# FinalAQsensors.net
KiCad netlist of a schematic drawn in EAGLE
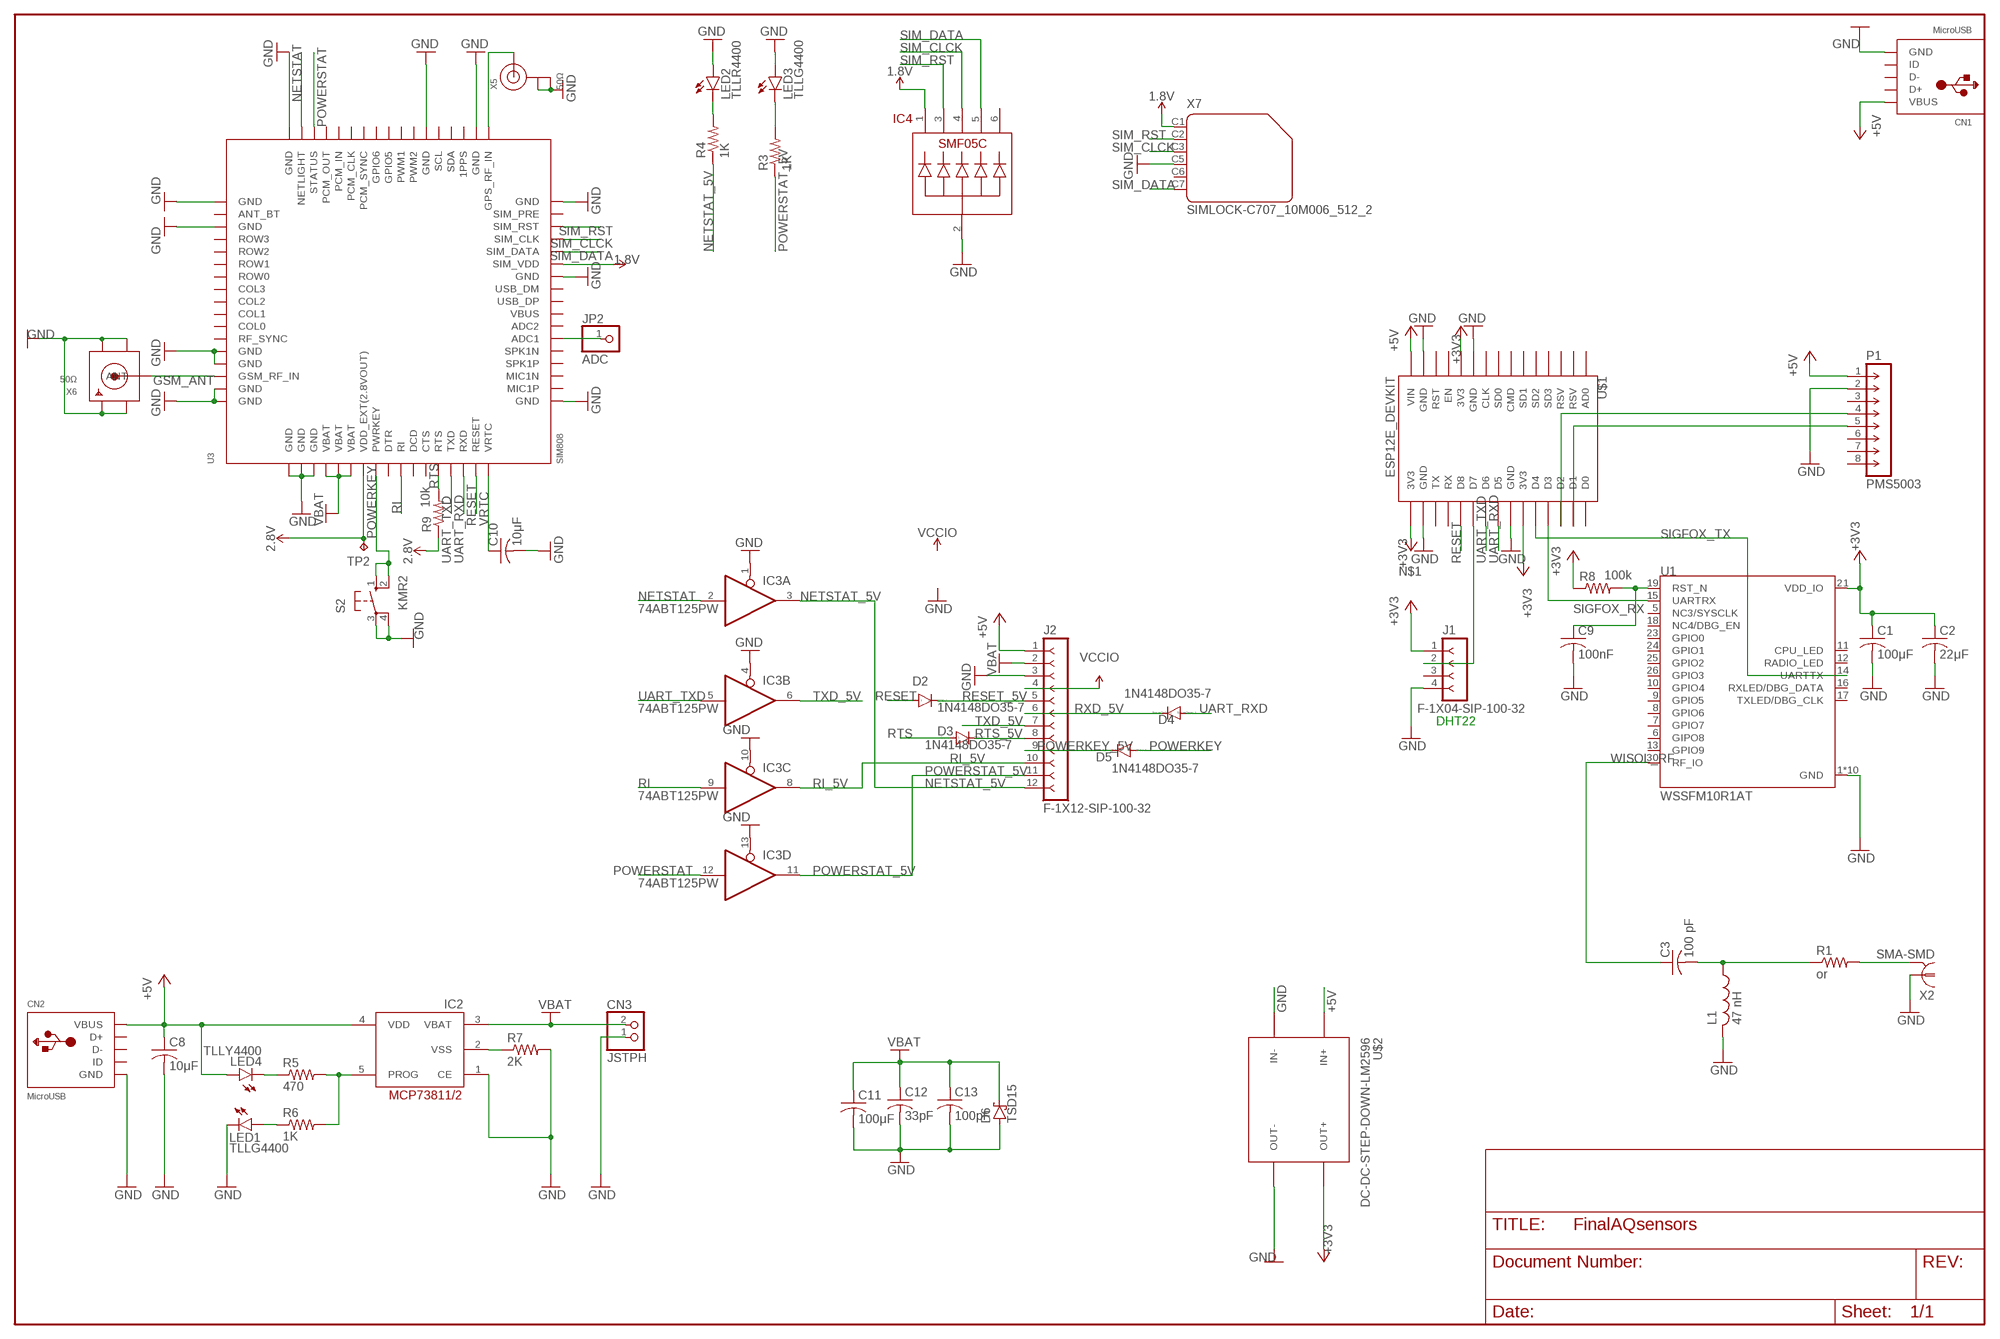
[diagram p0: schematic, sheet 1]

(export (version "E")
  (design (tool "Eeschema 10.0.6"))
  (components
    (comp (ref "C1")
      (value "100μF")
      (footprint "eagle-import:C0201")
      (libsource (lib "eagle-import") (part "C-USC0201"))
    )
    (comp (ref "C2")
      (value "22μF")
      (footprint "eagle-import:C0201")
      (libsource (lib "eagle-import") (part "C-USC0201"))
    )
    (comp (ref "C3")
      (value "100 pF")
      (footprint "eagle-import:C0201")
      (libsource (lib "eagle-import") (part "C-USC0201"))
    )
    (comp (ref "C8")
      (value "10μF")
      (footprint "eagle-import:C025-025X050")
      (libsource (lib "eagle-import") (part "C-US025-025X050"))
    )
    (comp (ref "C9")
      (value "100nF")
      (footprint "eagle-import:C025-025X050")
      (libsource (lib "eagle-import") (part "rcl_334_C-US025-025X050"))
    )
    (comp (ref "C10")
      (value "10μF")
      (footprint "eagle-import:C0402")
      (libsource (lib "eagle-import") (part "rcl_334_C-USC0402"))
    )
    (comp (ref "C11")
      (value "100μF")
      (footprint "eagle-import:C0402")
      (libsource (lib "eagle-import") (part "rcl_334_C-USC0402"))
    )
    (comp (ref "C12")
      (value "33pF")
      (footprint "eagle-import:C0402")
      (libsource (lib "eagle-import") (part "rcl_334_C-USC0402"))
    )
    (comp (ref "C13")
      (value "100pF")
      (footprint "eagle-import:C0402")
      (libsource (lib "eagle-import") (part "rcl_334_C-USC0402"))
    )
    (comp (ref "CN1")
      (value "MicroUSB")
      (footprint "eagle-import:USB-MINIB")
      (libsource (lib "eagle-import") (part "adafruit_420_USBMINIB"))
    )
    (comp (ref "CN2")
      (value "MicroUSB")
      (footprint "eagle-import:USB-MINIB")
      (libsource (lib "eagle-import") (part "USBMINIB"))
    )
    (comp (ref "CN3")
      (value "JSTPH")
      (footprint "eagle-import:JST-PH-2-SMT")
      (libsource (lib "eagle-import") (part "JST_2PIN-SMT"))
    )
    (comp (ref "D2")
      (value "1N4148DO35-7")
      (footprint "eagle-import:DO35-7")
      (libsource (lib "eagle-import") (part "1N4148DO35-7"))
    )
    (comp (ref "D3")
      (value "1N4148DO35-7")
      (footprint "eagle-import:DO35-7")
      (libsource (lib "eagle-import") (part "1N4148DO35-7"))
    )
    (comp (ref "D4")
      (value "1N4148DO35-7")
      (footprint "eagle-import:DO35-7")
      (libsource (lib "eagle-import") (part "1N4148DO35-7"))
    )
    (comp (ref "D5")
      (value "1N4148DO35-7")
      (footprint "eagle-import:DO35-7")
      (libsource (lib "eagle-import") (part "1N4148DO35-7"))
    )
    (comp (ref "D6")
      (value "TSD15")
      (footprint "eagle-import:CB429-15")
      (libsource (lib "eagle-import") (part "TSD15"))
    )
    (comp (ref "IC2")
      (value "MCP73811/2")
      (footprint "eagle-import:SOT23-5L")
      (libsource (lib "eagle-import") (part "MCP73811/2"))
    )
    (comp (ref "IC3")
      (value "74ABT125PW")
      (footprint "eagle-import:TSSOP14")
      (libsource (lib "eagle-import") (part "74125PWABT"))
    )
    (comp (ref "IC4")
      (value "SMF05C")
      (footprint "eagle-import:SC-70-6")
      (libsource (lib "eagle-import") (part "SMF05C"))
    )
    (comp (ref "J1")
      (value "F-1X04-SIP-100-32")
      (footprint "eagle-import:SIP-100-04-32")
      (libsource (lib "eagle-import") (part "F-1X04-SIP-100-32"))
    )
    (comp (ref "J2")
      (value "F-1X12-SIP-100-32")
      (footprint "eagle-import:SIP-100-12-32")
      (libsource (lib "eagle-import") (part "F-1X12-SIP-100-32"))
    )
    (comp (ref "JP2")
      (value "ADC")
      (footprint "eagle-import:1X01M")
      (libsource (lib "eagle-import") (part "PINHD-1X01_2.00"))
    )
    (comp (ref "L1")
      (value "47 nH")
      (footprint "eagle-import:0204_7")
      (libsource (lib "eagle-import") (part "L-US0204/7"))
    )
    (comp (ref "LED1")
      (value "TLLG4400")
      (footprint "eagle-import:LED3MM")
      (fields (field (name "MF") "VISHAY SEMICONDUCTOR"))
      (libsource (lib "eagle-import") (part "TLLG4400"))
    )
    (comp (ref "LED2")
      (value "TLLR4400")
      (footprint "eagle-import:LED3MM")
      (fields (field (name "MF") "VISHAY SEMICONDUCTOR"))
      (libsource (lib "eagle-import") (part "TLLR4400"))
    )
    (comp (ref "LED3")
      (value "TLLG4400")
      (footprint "eagle-import:LED3MM")
      (fields (field (name "MF") "VISHAY SEMICONDUCTOR"))
      (libsource (lib "eagle-import") (part "TLLG4400"))
    )
    (comp (ref "LED4")
      (value "TLLY4400")
      (footprint "eagle-import:LED3MM")
      (fields (field (name "MF") "VISHAY SEMICONDUCTOR"))
      (libsource (lib "eagle-import") (part "TLLY4400"))
    )
    (comp (ref "P1")
      (value "PMS5003")
      (footprint "eagle-import:SIP-100-08-40")
      (libsource (lib "eagle-import") (part "M-1X08-SIP-100-40"))
    )
    (comp (ref "R1")
      (value "or")
      (footprint "eagle-import:0204_5")
      (libsource (lib "eagle-import") (part "R-US_0204/5"))
    )
    (comp (ref "R3")
      (value "1K")
      (footprint "eagle-import:0204_5")
      (libsource (lib "eagle-import") (part "R-US_0204/5"))
    )
    (comp (ref "R4")
      (value "1K")
      (footprint "eagle-import:0204_5")
      (libsource (lib "eagle-import") (part "R-US_0204/5"))
    )
    (comp (ref "R5")
      (value "470")
      (footprint "eagle-import:0204_5")
      (libsource (lib "eagle-import") (part "R-US_0204/5"))
    )
    (comp (ref "R6")
      (value "1K")
      (footprint "eagle-import:0204_5")
      (libsource (lib "eagle-import") (part "R-US_0204/5"))
    )
    (comp (ref "R7")
      (value "2K")
      (footprint "eagle-import:0204_5")
      (libsource (lib "eagle-import") (part "R-US_0204/5"))
    )
    (comp (ref "R8")
      (value "100k")
      (footprint "eagle-import:0204_7")
      (libsource (lib "eagle-import") (part "R-US_0204/7"))
    )
    (comp (ref "R9")
      (value "10k")
      (footprint "eagle-import:0204_5")
      (libsource (lib "eagle-import") (part "R-US_0204/5"))
    )
    (comp (ref "S2")
      (value "KMR2")
      (footprint "eagle-import:B3F_40XX")
      (libsource (lib "eagle-import") (part "40/XX"))
    )
    (comp (ref "TP2")
      (value "TPTP10R")
      (footprint "eagle-import:TP10R")
      (libsource (lib "eagle-import") (part "TPTP10R"))
    )
    (comp (ref "U$1")
      (value "ESP12E_DEVKIT")
      (footprint "eagle-import:ESP12E_DEVKIT")
      (libsource (lib "eagle-import") (part "ESP12E_DEVKIT"))
    )
    (comp (ref "U$2")
      (value "DC-DC-STEP-DOWN-LM2596")
      (footprint "eagle-import:DC-DC-STEP-DOWN-LM2596")
      (libsource (lib "eagle-import") (part "DC-DC-STEP-DOWN-LM2596"))
    )
    (comp (ref "U1")
      (value "WSSFM10R1AT")
      (footprint "eagle-import:XCVR_WSSFM10R1AT")
      (fields (field (name "MF") "Avnet Design Services"))
      (libsource (lib "eagle-import") (part "WSSFM10R1AT"))
    )
    (comp (ref "U3")
      (value "SIM808")
      (footprint "eagle-import:SIM900_SMT")
      (libsource (lib "eagle-import") (part "GSM_SIM808_LITERAL"))
    )
    (comp (ref "X2")
      (value "SMA-SMD")
      (footprint "eagle-import:SMA-SMD")
      (libsource (lib "eagle-import") (part "SMA-SMD"))
    )
    (comp (ref "X5")
      (value "50Ω")
      (footprint "eagle-import:U.FL")
      (libsource (lib "eagle-import") (part "ANTENNA_U.FL"))
    )
    (comp (ref "X6")
      (value "50Ω")
      (footprint "eagle-import:SMA_EDGELAUNCH_UFL")
      (libsource (lib "eagle-import") (part "SMACONNECTOR_EDGE_UFL"))
    )
    (comp (ref "X7")
      (value "SIMLOCK-C707_10M006_512_2")
      (footprint "eagle-import:C707_10M006_512_2")
      (libsource (lib "eagle-import") (part "SIMLOCK-C707_10M006_512_2"))
    )
  )
  (nets
    (net (code "1") (name "+3V3") (class "Default")
      (node (ref "C1") (pin "1") (pinfunction "1_1") (pintype "passive"))
      (node (ref "C2") (pin "1") (pinfunction "1_1") (pintype "passive"))
      (node (ref "J1") (pin "1") (pinfunction "1_1") (pintype "passive"))
      (node (ref "R8") (pin "1") (pinfunction "1_1") (pintype "passive"))
      (node (ref "U$1") (pin "3V3@0") (pinfunction "3V3_3V3@0") (pintype "bidirectional"))
      (node (ref "U$1") (pin "3V3@1") (pinfunction "3V3_3V3@1") (pintype "bidirectional"))
      (node (ref "U$1") (pin "3V3@2") (pinfunction "3V3_3V3@2") (pintype "bidirectional"))
      (node (ref "U$2") (pin "OUT+") (pinfunction "OUT+_OUT+") (pintype "bidirectional"))
      (node (ref "U1") (pin "21") (pinfunction "VDD_IO_21") (pintype "power_in"))
    )
    (net (code "2") (name "+5V") (class "Default")
      (node (ref "C8") (pin "1") (pinfunction "1_1") (pintype "passive"))
      (node (ref "CN1") (pin "VBUS") (pinfunction "VBUS_VBUS") (pintype "power_in"))
      (node (ref "CN2") (pin "VBUS") (pinfunction "VBUS_VBUS") (pintype "power_in"))
      (node (ref "IC2") (pin "4") (pinfunction "VDD_4") (pintype "power_in"))
      (node (ref "J2") (pin "1") (pinfunction "1_1") (pintype "passive"))
      (node (ref "LED4") (pin "A") (pinfunction "A_A") (pintype "passive"))
      (node (ref "P1") (pin "1") (pinfunction "1_1") (pintype "passive"))
      (node (ref "U$1") (pin "VIN") (pinfunction "VIN_VIN") (pintype "bidirectional"))
      (node (ref "U$2") (pin "IN+") (pinfunction "IN+_IN+") (pintype "bidirectional"))
    )
    (net (code "3") (name "/GSM_ANT") (class "Default")
      (node (ref "U3") (pin "P$66") (pinfunction "GSM_RF_IN_P$66") (pintype "input"))
      (node (ref "X6") (pin "P") (pinfunction "ANT_P") (pintype "bidirectional"))
    )
    (net (code "4") (name "/N$1") (class "Default")
      (node (ref "J1") (pin "2") (pinfunction "2_2") (pintype "passive"))
      (node (ref "U$1") (pin "D7") (pinfunction "D7_D7") (pintype "bidirectional"))
    )
    (net (code "5") (name "/NETSTAT") (class "Default")
      (node (ref "IC3") (pin "2") (pinfunction "I_2") (pintype "input"))
      (node (ref "U3") (pin "P$50") (pinfunction "NETLIGHT_P$50") (pintype "output"))
    )
    (net (code "6") (name "/NETSTAT_5V") (class "Default")
      (node (ref "IC3") (pin "3") (pinfunction "O_3") (pintype "tri_state"))
      (node (ref "J2") (pin "12") (pinfunction "12_12") (pintype "passive"))
      (node (ref "R4") (pin "1") (pinfunction "1_1") (pintype "passive"))
    )
    (net (code "7") (name "/POWERKEY") (class "Default")
      (node (ref "D5") (pin "A") (pinfunction "A_A") (pintype "passive"))
      (node (ref "S2") (pin "1") (pinfunction "S_1") (pintype "passive"))
      (node (ref "S2") (pin "2") (pinfunction "S1_2") (pintype "passive"))
      (node (ref "U3") (pin "P$8") (pinfunction "PWRKEY_P$8") (pintype "input"))
    )
    (net (code "8") (name "/POWERKEY_5V") (class "Default")
      (node (ref "D5") (pin "C") (pinfunction "C_C") (pintype "passive"))
      (node (ref "J2") (pin "9") (pinfunction "9_9") (pintype "passive"))
    )
    (net (code "9") (name "/POWERSTAT") (class "Default")
      (node (ref "IC3") (pin "12") (pinfunction "I_12") (pintype "input"))
      (node (ref "U3") (pin "P$49") (pinfunction "STATUS_P$49") (pintype "output"))
    )
    (net (code "10") (name "/POWERSTAT_5V") (class "Default")
      (node (ref "IC3") (pin "11") (pinfunction "O_11") (pintype "tri_state"))
      (node (ref "J2") (pin "11") (pinfunction "11_11") (pintype "passive"))
      (node (ref "R3") (pin "1") (pinfunction "1_1") (pintype "passive"))
    )
    (net (code "11") (name "/RESET") (class "Default")
      (node (ref "D2") (pin "A") (pinfunction "A_A") (pintype "passive"))
      (node (ref "U$1") (pin "D8") (pinfunction "D8_D8") (pintype "bidirectional"))
      (node (ref "U3") (pin "P$16") (pinfunction "RESET_P$16") (pintype "input"))
    )
    (net (code "12") (name "/RESET_5V") (class "Default")
      (node (ref "D2") (pin "C") (pinfunction "C_C") (pintype "passive"))
      (node (ref "J2") (pin "5") (pinfunction "5_5") (pintype "passive"))
    )
    (net (code "13") (name "/RI") (class "Default")
      (node (ref "IC3") (pin "9") (pinfunction "I_9") (pintype "input"))
      (node (ref "U3") (pin "P$10") (pinfunction "RI_P$10") (pintype "output"))
    )
    (net (code "14") (name "/RI_5V") (class "Default")
      (node (ref "IC3") (pin "8") (pinfunction "O_8") (pintype "tri_state"))
      (node (ref "J2") (pin "10") (pinfunction "10_10") (pintype "passive"))
    )
    (net (code "15") (name "/RTS") (class "Default")
      (node (ref "D3") (pin "A") (pinfunction "A_A") (pintype "passive"))
      (node (ref "R9") (pin "2") (pinfunction "2_2") (pintype "passive"))
      (node (ref "U3") (pin "P$13") (pinfunction "RTS_P$13") (pintype "input"))
    )
    (net (code "16") (name "/RTS_5V") (class "Default")
      (node (ref "D3") (pin "C") (pinfunction "C_C") (pintype "passive"))
      (node (ref "J2") (pin "8") (pinfunction "8_8") (pintype "passive"))
    )
    (net (code "17") (name "/RXD_5V") (class "Default")
      (node (ref "D4") (pin "C") (pinfunction "C_C") (pintype "passive"))
      (node (ref "J2") (pin "6") (pinfunction "6_6") (pintype "passive"))
    )
    (net (code "18") (name "/SIGFOX_RX") (class "Default")
      (node (ref "U$1") (pin "D3") (pinfunction "D3_D3") (pintype "bidirectional"))
      (node (ref "U1") (pin "15") (pinfunction "UARTRX_15") (pintype "input"))
    )
    (net (code "19") (name "/SIGFOX_TX") (class "Default")
      (node (ref "U$1") (pin "D4") (pinfunction "D4_D4") (pintype "bidirectional"))
      (node (ref "U1") (pin "14") (pinfunction "UARTTX_14") (pintype "output"))
    )
    (net (code "20") (name "/SIM_CLCK") (class "Default")
      (node (ref "IC4") (pin "4") (pinfunction "4_4") (pintype "bidirectional"))
      (node (ref "U3") (pin "P$31") (pinfunction "SIM_CLK_P$31") (pintype "output"))
      (node (ref "X7") (pin "C3") (pinfunction "3_C3") (pintype "passive"))
    )
    (net (code "21") (name "/SIM_DATA") (class "Default")
      (node (ref "IC4") (pin "5") (pinfunction "5_5") (pintype "bidirectional"))
      (node (ref "U3") (pin "P$30") (pinfunction "SIM_DATA_P$30") (pintype "bidirectional"))
      (node (ref "X7") (pin "C7") (pinfunction "6_C7") (pintype "passive"))
    )
    (net (code "22") (name "/SIM_RST") (class "Default")
      (node (ref "IC4") (pin "3") (pinfunction "3_3") (pintype "bidirectional"))
      (node (ref "U3") (pin "P$32") (pinfunction "SIM_RST_P$32") (pintype "output"))
      (node (ref "X7") (pin "C2") (pinfunction "2_C2") (pintype "passive"))
    )
    (net (code "23") (name "/TXD_5V") (class "Default")
      (node (ref "IC3") (pin "6") (pinfunction "O_6") (pintype "tri_state"))
      (node (ref "J2") (pin "7") (pinfunction "7_7") (pintype "passive"))
    )
    (net (code "24") (name "/UART_RXD") (class "Default")
      (node (ref "D4") (pin "A") (pinfunction "A_A") (pintype "passive"))
      (node (ref "U$1") (pin "D5") (pinfunction "D5_D5") (pintype "bidirectional"))
      (node (ref "U3") (pin "P$15") (pinfunction "RXD_P$15") (pintype "input"))
    )
    (net (code "25") (name "/UART_TXD") (class "Default")
      (node (ref "IC3") (pin "5") (pinfunction "I_5") (pintype "input"))
      (node (ref "U$1") (pin "D6") (pinfunction "D6_D6") (pintype "bidirectional"))
      (node (ref "U3") (pin "P$14") (pinfunction "TXD_P$14") (pintype "output"))
    )
    (net (code "26") (name "/VBUS") (class "Default")
      (node (ref "U3") (pin "P$25") (pinfunction "VBUS_P$25") (pintype "power_in"))
    )
    (net (code "27") (name "/VRTC") (class "Default")
      (node (ref "C10") (pin "1") (pinfunction "1_1") (pintype "passive"))
      (node (ref "U3") (pin "P$17") (pinfunction "VRTC_P$17") (pintype "power_in"))
    )
    (net (code "28") (name "/WISOL_RF") (class "Default")
      (node (ref "C3") (pin "1") (pinfunction "1_1") (pintype "passive"))
      (node (ref "U1") (pin "30") (pinfunction "RF_IO_30") (pintype "bidirectional"))
    )
    (net (code "29") (name "1.8V") (class "Default")
      (node (ref "IC4") (pin "1") (pinfunction "1_1") (pintype "bidirectional"))
      (node (ref "U3") (pin "P$29") (pinfunction "SIM_VDD_P$29") (pintype "power_in"))
      (node (ref "X7") (pin "C1") (pinfunction "1_C1") (pintype "passive"))
    )
    (net (code "30") (name "2.8V") (class "Default")
      (node (ref "R9") (pin "1") (pinfunction "1_1") (pintype "passive"))
      (node (ref "TP2") (pin "TP") (pinfunction "TP_TP") (pintype "input"))
      (node (ref "U3") (pin "P$7") (pinfunction "VDD_EXT(2.8VOUT)_P$7") (pintype "power_in"))
    )
    (net (code "31") (name "GND") (class "Default")
      (node (ref "C1") (pin "2") (pinfunction "2_2") (pintype "passive"))
      (node (ref "C10") (pin "2") (pinfunction "2_2") (pintype "passive"))
      (node (ref "C11") (pin "2") (pinfunction "2_2") (pintype "passive"))
      (node (ref "C12") (pin "2") (pinfunction "2_2") (pintype "passive"))
      (node (ref "C13") (pin "2") (pinfunction "2_2") (pintype "passive"))
      (node (ref "C2") (pin "2") (pinfunction "2_2") (pintype "passive"))
      (node (ref "C8") (pin "2") (pinfunction "2_2") (pintype "passive"))
      (node (ref "C9") (pin "2") (pinfunction "2_2") (pintype "passive"))
      (node (ref "CN1") (pin "GND") (pinfunction "GND_GND") (pintype "power_in"))
      (node (ref "CN2") (pin "GND") (pinfunction "GND_GND") (pintype "power_in"))
      (node (ref "CN3") (pin "1") (pinfunction "2_1") (pintype "passive"))
      (node (ref "D6") (pin "A") (pinfunction "A_A") (pintype "passive"))
      (node (ref "IC2") (pin "1") (pinfunction "CE_1") (pintype "input"))
      (node (ref "IC3") (pin "1") (pinfunction "OE_1") (pintype "input"))
      (node (ref "IC3") (pin "10") (pinfunction "OE_10") (pintype "input"))
      (node (ref "IC3") (pin "13") (pinfunction "OE_13") (pintype "input"))
      (node (ref "IC3") (pin "4") (pinfunction "OE_4") (pintype "input"))
      (node (ref "IC4") (pin "2") (pinfunction "2_2") (pintype "bidirectional"))
      (node (ref "J1") (pin "4") (pinfunction "4_4") (pintype "passive"))
      (node (ref "J2") (pin "3") (pinfunction "3_3") (pintype "passive"))
      (node (ref "L1") (pin "2") (pinfunction "2_2") (pintype "passive"))
      (node (ref "LED1") (pin "K") (pinfunction "C_K") (pintype "passive"))
      (node (ref "LED2") (pin "A") (pinfunction "A_A") (pintype "passive"))
      (node (ref "LED3") (pin "A") (pinfunction "A_A") (pintype "passive"))
      (node (ref "P1") (pin "2") (pinfunction "2_2") (pintype "passive"))
      (node (ref "R7") (pin "2") (pinfunction "2_2") (pintype "passive"))
      (node (ref "S2") (pin "3") (pinfunction "P_3") (pintype "passive"))
      (node (ref "S2") (pin "4") (pinfunction "P1_4") (pintype "passive"))
      (node (ref "U$1") (pin "GND@0") (pinfunction "GND_GND@0") (pintype "bidirectional"))
      (node (ref "U$1") (pin "GND@1") (pinfunction "GND_GND@1") (pintype "bidirectional"))
      (node (ref "U$1") (pin "GND@2") (pinfunction "GND_GND@2") (pintype "bidirectional"))
      (node (ref "U$1") (pin "GND@3") (pinfunction "GND_GND@3") (pintype "bidirectional"))
      (node (ref "U$2") (pin "IN-") (pinfunction "IN-_IN-") (pintype "bidirectional"))
      (node (ref "U$2") (pin "OUT-") (pinfunction "OUT-_OUT-") (pintype "bidirectional"))
      (node (ref "U1") (pin "1") (pinfunction "GND_1") (pintype "power_in"))
      (node (ref "U1") (pin "2") (pinfunction "GND_2") (pintype "power_in"))
      (node (ref "U1") (pin "20") (pinfunction "GND_20") (pintype "power_in"))
      (node (ref "U1") (pin "22") (pinfunction "GND_22") (pintype "power_in"))
      (node (ref "U1") (pin "27") (pinfunction "GND_27") (pintype "power_in"))
      (node (ref "U1") (pin "28") (pinfunction "GND_28") (pintype "power_in"))
      (node (ref "U1") (pin "29") (pinfunction "GND_29") (pintype "power_in"))
      (node (ref "U1") (pin "3") (pinfunction "GND_3") (pintype "power_in"))
      (node (ref "U1") (pin "31") (pinfunction "GND_31") (pintype "power_in"))
      (node (ref "U1") (pin "4") (pinfunction "GND_4") (pintype "power_in"))
      (node (ref "U3") (pin "P$1") (pinfunction "GND_P$1") (pintype "power_in"))
      (node (ref "U3") (pin "P$18") (pinfunction "GND_P$18") (pintype "power_in"))
      (node (ref "U3") (pin "P$2") (pinfunction "GND_P$2") (pintype "power_in"))
      (node (ref "U3") (pin "P$28") (pinfunction "GND_P$28") (pintype "power_in"))
      (node (ref "U3") (pin "P$3") (pinfunction "GND_P$3") (pintype "power_in"))
      (node (ref "U3") (pin "P$34") (pinfunction "GND_P$34") (pintype "power_in"))
      (node (ref "U3") (pin "P$36") (pinfunction "GND_P$36") (pintype "power_in"))
      (node (ref "U3") (pin "P$40") (pinfunction "GND_P$40") (pintype "power_in"))
      (node (ref "U3") (pin "P$51") (pinfunction "GND_P$51") (pintype "power_in"))
      (node (ref "U3") (pin "P$52") (pinfunction "GND_P$52") (pintype "power_in"))
      (node (ref "U3") (pin "P$54") (pinfunction "GND_P$54") (pintype "power_in"))
      (node (ref "U3") (pin "P$64") (pinfunction "GND_P$64") (pintype "power_in"))
      (node (ref "U3") (pin "P$65") (pinfunction "GND_P$65") (pintype "power_in"))
      (node (ref "U3") (pin "P$67") (pinfunction "GND_P$67") (pintype "power_in"))
      (node (ref "U3") (pin "P$68") (pinfunction "GND_P$68") (pintype "power_in"))
      (node (ref "X2") (pin "1") (pinfunction "1_1") (pintype "passive"))
      (node (ref "X5") (pin "1") (pinfunction "GND_1") (pintype "passive"))
      (node (ref "X5") (pin "2") (pinfunction "GND_2") (pintype "passive"))
      (node (ref "X6") (pin "GND@1") (pinfunction "GND1_GND@1") (pintype "power_in"))
      (node (ref "X6") (pin "GND@2") (pinfunction "GND2_GND@2") (pintype "power_in"))
      (node (ref "X6") (pin "GND@3") (pinfunction "GND3_GND@3") (pintype "power_in"))
      (node (ref "X6") (pin "GND@4") (pinfunction "GND4_GND@4") (pintype "power_in"))
      (node (ref "X7") (pin "C5") (pinfunction "4_C5") (pintype "passive"))
    )
    (net (code "32") (name "Net-(C3-Pad2)") (class "Default")
      (node (ref "C3") (pin "2") (pinfunction "2_2") (pintype "passive"))
      (node (ref "L1") (pin "1") (pinfunction "1_1") (pintype "passive"))
      (node (ref "R1") (pin "1") (pinfunction "1_1") (pintype "passive"))
    )
    (net (code "33") (name "Net-(IC2-PROG)") (class "Default")
      (node (ref "IC2") (pin "5") (pinfunction "PROG_5") (pintype "input"))
      (node (ref "R5") (pin "2") (pinfunction "2_2") (pintype "passive"))
      (node (ref "R6") (pin "2") (pinfunction "2_2") (pintype "passive"))
    )
    (net (code "34") (name "Net-(IC2-VSS)") (class "Default")
      (node (ref "IC2") (pin "2") (pinfunction "VSS_2") (pintype "power_in"))
      (node (ref "R7") (pin "1") (pinfunction "1_1") (pintype "passive"))
    )
    (net (code "35") (name "Net-(LED1-PadA)") (class "Default")
      (node (ref "LED1") (pin "A") (pinfunction "A_A") (pintype "passive"))
      (node (ref "R6") (pin "1") (pinfunction "1_1") (pintype "passive"))
    )
    (net (code "36") (name "Net-(LED2-C)") (class "Default")
      (node (ref "LED2") (pin "K") (pinfunction "C_K") (pintype "passive"))
      (node (ref "R4") (pin "2") (pinfunction "2_2") (pintype "passive"))
    )
    (net (code "37") (name "Net-(LED3-C)") (class "Default")
      (node (ref "LED3") (pin "K") (pinfunction "C_K") (pintype "passive"))
      (node (ref "R3") (pin "2") (pinfunction "2_2") (pintype "passive"))
    )
    (net (code "38") (name "Net-(LED4-C)") (class "Default")
      (node (ref "LED4") (pin "K") (pinfunction "C_K") (pintype "passive"))
      (node (ref "R5") (pin "1") (pinfunction "1_1") (pintype "passive"))
    )
    (net (code "39") (name "Net-(P1-Pad4)") (class "Default")
      (node (ref "P1") (pin "4") (pinfunction "4_4") (pintype "passive"))
      (node (ref "U$1") (pin "D2") (pinfunction "D2_D2") (pintype "bidirectional"))
    )
    (net (code "40") (name "Net-(P1-Pad5)") (class "Default")
      (node (ref "P1") (pin "5") (pinfunction "5_5") (pintype "passive"))
      (node (ref "U$1") (pin "D1") (pinfunction "D1_D1") (pintype "bidirectional"))
    )
    (net (code "41") (name "Net-(R1-Pad2)") (class "Default")
      (node (ref "R1") (pin "2") (pinfunction "2_2") (pintype "passive"))
      (node (ref "X2") (pin "2@1") (pinfunction "2_2@1") (pintype "passive"))
      (node (ref "X2") (pin "2@2") (pinfunction "2_2@2") (pintype "passive"))
      (node (ref "X2") (pin "2@3") (pinfunction "2_2@3") (pintype "passive"))
      (node (ref "X2") (pin "2@4") (pinfunction "2_2@4") (pintype "passive"))
      (node (ref "X2") (pin "2@5") (pinfunction "2_2@5") (pintype "passive"))
      (node (ref "X2") (pin "2@6") (pinfunction "2_2@6") (pintype "passive"))
    )
    (net (code "42") (name "Net-(U1-RST_N)") (class "Default")
      (node (ref "C9") (pin "1") (pinfunction "1_1") (pintype "passive"))
      (node (ref "R8") (pin "2") (pinfunction "2_2") (pintype "passive"))
      (node (ref "U1") (pin "19") (pinfunction "RST_N_19") (pintype "input"))
    )
    (net (code "43") (name "Net-(U3-ADC1)") (class "Default")
      (node (ref "JP2") (pin "1") (pinfunction "1_1") (pintype "passive"))
      (node (ref "U3") (pin "P$23") (pinfunction "ADC1_P$23") (pintype "input"))
    )
    (net (code "44") (name "Net-(U3-GPS_RF_IN)") (class "Default")
      (node (ref "U3") (pin "P$35") (pinfunction "GPS_RF_IN_P$35") (pintype "bidirectional"))
      (node (ref "X5") (pin "3") (pinfunction "SIGNAL_3") (pintype "passive"))
    )
    (net (code "45") (name "VBAT") (class "Default")
      (node (ref "C11") (pin "1") (pinfunction "1_1") (pintype "passive"))
      (node (ref "C12") (pin "1") (pinfunction "1_1") (pintype "passive"))
      (node (ref "C13") (pin "1") (pinfunction "1_1") (pintype "passive"))
      (node (ref "CN3") (pin "2") (pinfunction "1_2") (pintype "passive"))
      (node (ref "D6") (pin "C") (pinfunction "C_C") (pintype "passive"))
      (node (ref "IC2") (pin "3") (pinfunction "VBAT_3") (pintype "bidirectional"))
      (node (ref "J2") (pin "2") (pinfunction "2_2") (pintype "passive"))
      (node (ref "U3") (pin "P$4") (pinfunction "VBAT_P$4") (pintype "power_in"))
      (node (ref "U3") (pin "P$5") (pinfunction "VBAT_P$5") (pintype "power_in"))
      (node (ref "U3") (pin "P$6") (pinfunction "VBAT_P$6") (pintype "power_in"))
    )
    (net (code "46") (name "VCCIO") (class "Default")
      (node (ref "J2") (pin "4") (pinfunction "4_4") (pintype "passive"))
    )
    (net (code "47") (name "unconnected-(CN1-PadD+)") (class "Default")
      (node (ref "CN1") (pin "D+") (pinfunction "D+_D+") (pintype "bidirectional"))
    )
    (net (code "48") (name "unconnected-(CN1-PadD-)") (class "Default")
      (node (ref "CN1") (pin "D-") (pinfunction "D-_D-") (pintype "bidirectional"))
    )
    (net (code "49") (name "unconnected-(CN1-PadID)") (class "Default")
      (node (ref "CN1") (pin "ID") (pinfunction "ID_ID") (pintype "bidirectional"))
    )
    (net (code "50") (name "unconnected-(CN2-PadD+)") (class "Default")
      (node (ref "CN2") (pin "D+") (pinfunction "D+_D+") (pintype "bidirectional"))
    )
    (net (code "51") (name "unconnected-(CN2-PadD-)") (class "Default")
      (node (ref "CN2") (pin "D-") (pinfunction "D-_D-") (pintype "bidirectional"))
    )
    (net (code "52") (name "unconnected-(CN2-PadID)") (class "Default")
      (node (ref "CN2") (pin "ID") (pinfunction "ID_ID") (pintype "bidirectional"))
    )
    (net (code "53") (name "unconnected-(IC4-Pad6)") (class "Default")
      (node (ref "IC4") (pin "6") (pinfunction "6_6") (pintype "bidirectional"))
    )
    (net (code "54") (name "unconnected-(J1-Pad3)") (class "Default")
      (node (ref "J1") (pin "3") (pinfunction "3_3") (pintype "passive"))
    )
    (net (code "55") (name "unconnected-(P1-Pad3)") (class "Default")
      (node (ref "P1") (pin "3") (pinfunction "3_3") (pintype "passive"))
    )
    (net (code "56") (name "unconnected-(P1-Pad6)") (class "Default")
      (node (ref "P1") (pin "6") (pinfunction "6_6") (pintype "passive"))
    )
    (net (code "57") (name "unconnected-(P1-Pad7)") (class "Default")
      (node (ref "P1") (pin "7") (pinfunction "7_7") (pintype "passive"))
    )
    (net (code "58") (name "unconnected-(P1-Pad8)") (class "Default")
      (node (ref "P1") (pin "8") (pinfunction "8_8") (pintype "passive"))
    )
    (net (code "59") (name "unconnected-(U$1-PadAD0)") (class "Default")
      (node (ref "U$1") (pin "AD0") (pinfunction "AD0_AD0") (pintype "bidirectional"))
    )
    (net (code "60") (name "unconnected-(U$1-PadCLK)") (class "Default")
      (node (ref "U$1") (pin "CLK") (pinfunction "CLK_CLK") (pintype "bidirectional"))
    )
    (net (code "61") (name "unconnected-(U$1-PadCMD)") (class "Default")
      (node (ref "U$1") (pin "CMD") (pinfunction "CMD_CMD") (pintype "bidirectional"))
    )
    (net (code "62") (name "unconnected-(U$1-PadD0)") (class "Default")
      (node (ref "U$1") (pin "D0") (pinfunction "D0_D0") (pintype "bidirectional"))
    )
    (net (code "63") (name "unconnected-(U$1-PadEN)") (class "Default")
      (node (ref "U$1") (pin "EN") (pinfunction "EN_EN") (pintype "bidirectional"))
    )
    (net (code "64") (name "unconnected-(U$1-PadRST)") (class "Default")
      (node (ref "U$1") (pin "RST") (pinfunction "RST_RST") (pintype "bidirectional"))
    )
    (net (code "65") (name "unconnected-(U$1-PadRX)") (class "Default")
      (node (ref "U$1") (pin "RX") (pinfunction "RX_RX") (pintype "bidirectional"))
    )
    (net (code "66") (name "unconnected-(U$1-PadSD0)") (class "Default")
      (node (ref "U$1") (pin "SD0") (pinfunction "SD0_SD0") (pintype "bidirectional"))
    )
    (net (code "67") (name "unconnected-(U$1-PadSD1)") (class "Default")
      (node (ref "U$1") (pin "SD1") (pinfunction "SD1_SD1") (pintype "bidirectional"))
    )
    (net (code "68") (name "unconnected-(U$1-PadSD2)") (class "Default")
      (node (ref "U$1") (pin "SD2") (pinfunction "SD2_SD2") (pintype "bidirectional"))
    )
    (net (code "69") (name "unconnected-(U$1-PadSD3)") (class "Default")
      (node (ref "U$1") (pin "SD3") (pinfunction "SD3_SD3") (pintype "bidirectional"))
    )
    (net (code "70") (name "unconnected-(U$1-PadTX)") (class "Default")
      (node (ref "U$1") (pin "TX") (pinfunction "TX_TX") (pintype "bidirectional"))
    )
    (net (code "71") (name "unconnected-(U$1-RSV-PadRSV@0)") (class "Default")
      (node (ref "U$1") (pin "RSV@0") (pinfunction "RSV_RSV@0") (pintype "bidirectional"))
    )
    (net (code "72") (name "unconnected-(U$1-RSV-PadRSV@1)") (class "Default")
      (node (ref "U$1") (pin "RSV@1") (pinfunction "RSV_RSV@1") (pintype "bidirectional"))
    )
    (net (code "73") (name "unconnected-(U1-CPU_LED-Pad11)") (class "Default")
      (node (ref "U1") (pin "11") (pinfunction "CPU_LED_11") (pintype "output"))
    )
    (net (code "74") (name "unconnected-(U1-GIPO8-Pad6)") (class "Default")
      (node (ref "U1") (pin "6") (pinfunction "GIPO8_6") (pintype "bidirectional"))
    )
    (net (code "75") (name "unconnected-(U1-GPIO0-Pad23)") (class "Default")
      (node (ref "U1") (pin "23") (pinfunction "GPIO0_23") (pintype "bidirectional"))
    )
    (net (code "76") (name "unconnected-(U1-GPIO1-Pad24)") (class "Default")
      (node (ref "U1") (pin "24") (pinfunction "GPIO1_24") (pintype "bidirectional"))
    )
    (net (code "77") (name "unconnected-(U1-GPIO2-Pad25)") (class "Default")
      (node (ref "U1") (pin "25") (pinfunction "GPIO2_25") (pintype "bidirectional"))
    )
    (net (code "78") (name "unconnected-(U1-GPIO3-Pad26)") (class "Default")
      (node (ref "U1") (pin "26") (pinfunction "GPIO3_26") (pintype "bidirectional"))
    )
    (net (code "79") (name "unconnected-(U1-GPIO4-Pad10)") (class "Default")
      (node (ref "U1") (pin "10") (pinfunction "GPIO4_10") (pintype "input"))
    )
    (net (code "80") (name "unconnected-(U1-GPIO5-Pad9)") (class "Default")
      (node (ref "U1") (pin "9") (pinfunction "GPIO5_9") (pintype "bidirectional"))
    )
    (net (code "81") (name "unconnected-(U1-GPIO6-Pad8)") (class "Default")
      (node (ref "U1") (pin "8") (pinfunction "GPIO6_8") (pintype "bidirectional"))
    )
    (net (code "82") (name "unconnected-(U1-GPIO7-Pad7)") (class "Default")
      (node (ref "U1") (pin "7") (pinfunction "GPIO7_7") (pintype "bidirectional"))
    )
    (net (code "83") (name "unconnected-(U1-GPIO9-Pad13)") (class "Default")
      (node (ref "U1") (pin "13") (pinfunction "GPIO9_13") (pintype "input"))
    )
    (net (code "84") (name "unconnected-(U1-NC3{slash}SYSCLK-Pad5)") (class "Default")
      (node (ref "U1") (pin "5") (pinfunction "NC3/SYSCLK_5") (pintype "input"))
    )
    (net (code "85") (name "unconnected-(U1-NC4{slash}DBG_EN-Pad18)") (class "Default")
      (node (ref "U1") (pin "18") (pinfunction "NC4/DBG_EN_18") (pintype "input"))
    )
    (net (code "86") (name "unconnected-(U1-RADIO_LED-Pad12)") (class "Default")
      (node (ref "U1") (pin "12") (pinfunction "RADIO_LED_12") (pintype "output"))
    )
    (net (code "87") (name "unconnected-(U1-RXLED{slash}DBG_DATA-Pad16)") (class "Default")
      (node (ref "U1") (pin "16") (pinfunction "RXLED/DBG_DATA_16") (pintype "output"))
    )
    (net (code "88") (name "unconnected-(U1-TXLED{slash}DBG_CLK-Pad17)") (class "Default")
      (node (ref "U1") (pin "17") (pinfunction "TXLED/DBG_CLK_17") (pintype "output"))
    )
    (net (code "89") (name "unconnected-(U3-1PPS-PadP$37)") (class "Default")
      (node (ref "U3") (pin "P$37") (pinfunction "1PPS_P$37") (pintype "input"))
    )
    (net (code "90") (name "unconnected-(U3-ADC2-PadP$24)") (class "Default")
      (node (ref "U3") (pin "P$24") (pinfunction "ADC2_P$24") (pintype "input"))
    )
    (net (code "91") (name "unconnected-(U3-ANT_BT-PadP$53)") (class "Default")
      (node (ref "U3") (pin "P$53") (pinfunction "ANT_BT_P$53") (pintype "bidirectional"))
    )
    (net (code "92") (name "unconnected-(U3-COL0-PadP$62)") (class "Default")
      (node (ref "U3") (pin "P$62") (pinfunction "COL0_P$62") (pintype "input"))
    )
    (net (code "93") (name "unconnected-(U3-COL1-PadP$61)") (class "Default")
      (node (ref "U3") (pin "P$61") (pinfunction "COL1_P$61") (pintype "input"))
    )
    (net (code "94") (name "unconnected-(U3-COL2-PadP$60)") (class "Default")
      (node (ref "U3") (pin "P$60") (pinfunction "COL2_P$60") (pintype "input"))
    )
    (net (code "95") (name "unconnected-(U3-COL3-PadP$59)") (class "Default")
      (node (ref "U3") (pin "P$59") (pinfunction "COL3_P$59") (pintype "input"))
    )
    (net (code "96") (name "unconnected-(U3-CTS-PadP$12)") (class "Default")
      (node (ref "U3") (pin "P$12") (pinfunction "CTS_P$12") (pintype "output"))
    )
    (net (code "97") (name "unconnected-(U3-DCD-PadP$11)") (class "Default")
      (node (ref "U3") (pin "P$11") (pinfunction "DCD_P$11") (pintype "output"))
    )
    (net (code "98") (name "unconnected-(U3-DTR-PadP$9)") (class "Default")
      (node (ref "U3") (pin "P$9") (pinfunction "DTR_P$9") (pintype "input"))
    )
    (net (code "99") (name "unconnected-(U3-GPIO5-PadP$43)") (class "Default")
      (node (ref "U3") (pin "P$43") (pinfunction "GPIO5_P$43") (pintype "bidirectional"))
    )
    (net (code "100") (name "unconnected-(U3-GPIO6-PadP$44)") (class "Default")
      (node (ref "U3") (pin "P$44") (pinfunction "GPIO6_P$44") (pintype "bidirectional"))
    )
    (net (code "101") (name "unconnected-(U3-MIC1N-PadP$20)") (class "Default")
      (node (ref "U3") (pin "P$20") (pinfunction "MIC1N_P$20") (pintype "input"))
    )
    (net (code "102") (name "unconnected-(U3-MIC1P-PadP$19)") (class "Default")
      (node (ref "U3") (pin "P$19") (pinfunction "MIC1P_P$19") (pintype "input"))
    )
    (net (code "103") (name "unconnected-(U3-PCM_CLK-PadP$46)") (class "Default")
      (node (ref "U3") (pin "P$46") (pinfunction "PCM_CLK_P$46") (pintype "input"))
    )
    (net (code "104") (name "unconnected-(U3-PCM_IN-PadP$47)") (class "Default")
      (node (ref "U3") (pin "P$47") (pinfunction "PCM_IN_P$47") (pintype "input"))
    )
    (net (code "105") (name "unconnected-(U3-PCM_OUT-PadP$48)") (class "Default")
      (node (ref "U3") (pin "P$48") (pinfunction "PCM_OUT_P$48") (pintype "output"))
    )
    (net (code "106") (name "unconnected-(U3-PCM_SYNC-PadP$45)") (class "Default")
      (node (ref "U3") (pin "P$45") (pinfunction "PCM_SYNC_P$45") (pintype "output"))
    )
    (net (code "107") (name "unconnected-(U3-PWM1-PadP$42)") (class "Default")
      (node (ref "U3") (pin "P$42") (pinfunction "PWM1_P$42") (pintype "output"))
    )
    (net (code "108") (name "unconnected-(U3-PWM2-PadP$41)") (class "Default")
      (node (ref "U3") (pin "P$41") (pinfunction "PWM2_P$41") (pintype "output"))
    )
    (net (code "109") (name "unconnected-(U3-RF_SYNC-PadP$63)") (class "Default")
      (node (ref "U3") (pin "P$63") (pinfunction "RF_SYNC_P$63") (pintype "output"))
    )
    (net (code "110") (name "unconnected-(U3-ROW0-PadP$58)") (class "Default")
      (node (ref "U3") (pin "P$58") (pinfunction "ROW0_P$58") (pintype "output"))
    )
    (net (code "111") (name "unconnected-(U3-ROW1-PadP$57)") (class "Default")
      (node (ref "U3") (pin "P$57") (pinfunction "ROW1_P$57") (pintype "output"))
    )
    (net (code "112") (name "unconnected-(U3-ROW2-PadP$56)") (class "Default")
      (node (ref "U3") (pin "P$56") (pinfunction "ROW2_P$56") (pintype "output"))
    )
    (net (code "113") (name "unconnected-(U3-ROW3-PadP$55)") (class "Default")
      (node (ref "U3") (pin "P$55") (pinfunction "ROW3_P$55") (pintype "output"))
    )
    (net (code "114") (name "unconnected-(U3-SCL-PadP$39)") (class "Default")
      (node (ref "U3") (pin "P$39") (pinfunction "SCL_P$39") (pintype "output"))
    )
    (net (code "115") (name "unconnected-(U3-SDA-PadP$38)") (class "Default")
      (node (ref "U3") (pin "P$38") (pinfunction "SDA_P$38") (pintype "bidirectional"))
    )
    (net (code "116") (name "unconnected-(U3-SIM_PRE-PadP$33)") (class "Default")
      (node (ref "U3") (pin "P$33") (pinfunction "SIM_PRE_P$33") (pintype "input"))
    )
    (net (code "117") (name "unconnected-(U3-SPK1N-PadP$22)") (class "Default")
      (node (ref "U3") (pin "P$22") (pinfunction "SPK1N_P$22") (pintype "output"))
    )
    (net (code "118") (name "unconnected-(U3-SPK1P-PadP$21)") (class "Default")
      (node (ref "U3") (pin "P$21") (pinfunction "SPK1P_P$21") (pintype "output"))
    )
    (net (code "119") (name "unconnected-(U3-USB_DM-PadP$27)") (class "Default")
      (node (ref "U3") (pin "P$27") (pinfunction "USB_DM_P$27") (pintype "bidirectional"))
    )
    (net (code "120") (name "unconnected-(U3-USB_DP-PadP$26)") (class "Default")
      (node (ref "U3") (pin "P$26") (pinfunction "USB_DP_P$26") (pintype "bidirectional"))
    )
    (net (code "121") (name "unconnected-(X7-5-PadC6)") (class "Default")
      (node (ref "X7") (pin "C6") (pinfunction "5_C6") (pintype "passive"))
    )
  )
)
